# Sequential_LEDs.net
KiCad netlist of a schematic drawn in Altium Designer
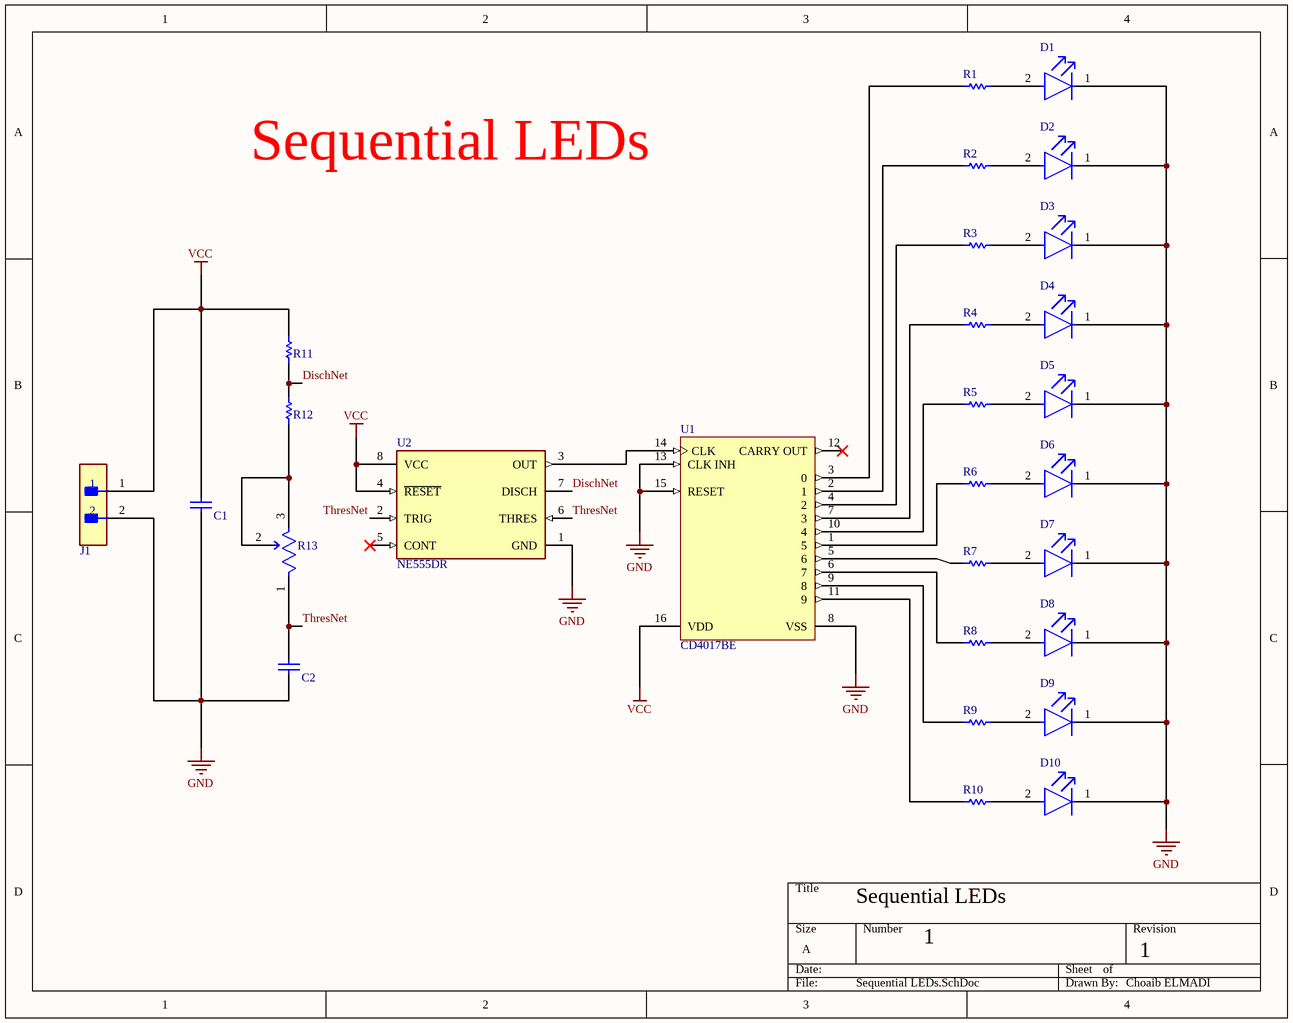
[diagram p0: Sequential LEDs.SchDoc]

(export (version "E")
  (design (tool "Eeschema 10.0.6"))
  (components
    (comp (ref "C1")
      (value "C0805C105K3RACTU")
      (footprint "CAPC2013X140X50LL20T25")
      (fields (field (name "MANUFACTURER") "Kemet"))
      (libsource (lib "Altium Content Vault") (part "CAP"))
    )
    (comp (ref "C2")
      (value "C0805C105K3RACTU")
      (footprint "CAPC2013X140X50LL20T25")
      (fields (field (name "MANUFACTURER") "Kemet"))
      (libsource (lib "Altium Content Vault") (part "CAP"))
    )
    (comp (ref "D1")
      (value "HLMP-1301")
      (footprint "FP-HLMP-1301-MFG")
      (description "LED RED DIFFUSED T-1 T/H")
      (fields
        (field (name "OCTOPART") "https://octopart.com/hlmp-1301-broadcom-71130345")
        (field (name "MANUFACTURER") "Broadcom")
      )
      (libsource (lib "Altium Content Vault") (part "8706943c75ba83719d021d2fdc84c58"))
    )
    (comp (ref "D2")
      (value "HLMP-1301")
      (footprint "FP-HLMP-1301-MFG")
      (description "LED RED DIFFUSED T-1 T/H")
      (fields
        (field (name "OCTOPART") "https://octopart.com/hlmp-1301-broadcom-71130345")
        (field (name "MANUFACTURER") "Broadcom")
      )
      (libsource (lib "Altium Content Vault") (part "8706943c75ba83719d021d2fdc84c58"))
    )
    (comp (ref "D3")
      (value "HLMP-1301")
      (footprint "FP-HLMP-1301-MFG")
      (description "LED RED DIFFUSED T-1 T/H")
      (fields
        (field (name "OCTOPART") "https://octopart.com/hlmp-1301-broadcom-71130345")
        (field (name "MANUFACTURER") "Broadcom")
      )
      (libsource (lib "Altium Content Vault") (part "8706943c75ba83719d021d2fdc84c58"))
    )
    (comp (ref "D4")
      (value "HLMP-1301")
      (footprint "FP-HLMP-1301-MFG")
      (description "LED RED DIFFUSED T-1 T/H")
      (fields
        (field (name "OCTOPART") "https://octopart.com/hlmp-1301-broadcom-71130345")
        (field (name "MANUFACTURER") "Broadcom")
      )
      (libsource (lib "Altium Content Vault") (part "8706943c75ba83719d021d2fdc84c58"))
    )
    (comp (ref "D5")
      (value "HLMP-1301")
      (footprint "FP-HLMP-1301-MFG")
      (description "LED RED DIFFUSED T-1 T/H")
      (fields
        (field (name "OCTOPART") "https://octopart.com/hlmp-1301-broadcom-71130345")
        (field (name "MANUFACTURER") "Broadcom")
      )
      (libsource (lib "Altium Content Vault") (part "8706943c75ba83719d021d2fdc84c58"))
    )
    (comp (ref "D6")
      (value "HLMP-1301")
      (footprint "FP-HLMP-1301-MFG")
      (description "LED RED DIFFUSED T-1 T/H")
      (fields
        (field (name "OCTOPART") "https://octopart.com/hlmp-1301-broadcom-71130345")
        (field (name "MANUFACTURER") "Broadcom")
      )
      (libsource (lib "Altium Content Vault") (part "8706943c75ba83719d021d2fdc84c58"))
    )
    (comp (ref "D7")
      (value "HLMP-1301")
      (footprint "FP-HLMP-1301-MFG")
      (description "LED RED DIFFUSED T-1 T/H")
      (fields
        (field (name "OCTOPART") "https://octopart.com/hlmp-1301-broadcom-71130345")
        (field (name "MANUFACTURER") "Broadcom")
      )
      (libsource (lib "Altium Content Vault") (part "8706943c75ba83719d021d2fdc84c58"))
    )
    (comp (ref "D8")
      (value "HLMP-1301")
      (footprint "FP-HLMP-1301-MFG")
      (description "LED RED DIFFUSED T-1 T/H")
      (fields
        (field (name "OCTOPART") "https://octopart.com/hlmp-1301-broadcom-71130345")
        (field (name "MANUFACTURER") "Broadcom")
      )
      (libsource (lib "Altium Content Vault") (part "8706943c75ba83719d021d2fdc84c58"))
    )
    (comp (ref "D9")
      (value "HLMP-1301")
      (footprint "FP-HLMP-1301-MFG")
      (description "LED RED DIFFUSED T-1 T/H")
      (fields
        (field (name "OCTOPART") "https://octopart.com/hlmp-1301-broadcom-71130345")
        (field (name "MANUFACTURER") "Broadcom")
      )
      (libsource (lib "Altium Content Vault") (part "8706943c75ba83719d021d2fdc84c58"))
    )
    (comp (ref "D10")
      (value "HLMP-1301")
      (footprint "FP-HLMP-1301-MFG")
      (description "LED RED DIFFUSED T-1 T/H")
      (fields
        (field (name "OCTOPART") "https://octopart.com/hlmp-1301-broadcom-71130345")
        (field (name "MANUFACTURER") "Broadcom")
      )
      (libsource (lib "Altium Content Vault") (part "8706943c75ba83719d021d2fdc84c58"))
    )
    (comp (ref "J1")
      (value "M20-9990245")
      (footprint "FP-M20-9990245-MFG")
      (description "CONN HEADER VERT 2POS 2.54MM")
      (fields (field (name "VOLTAGE") "50V"))
      (libsource (lib "Altium Content Vault") (part "3bc925449376181038e59eaffc5286c"))
    )
    (comp (ref "R1")
      (value "RC0805FR-071KL")
      (footprint "RESC2013X60X35ML10T20")
      (description "Chip Resistor, 1 KOhm, +/- 1%, 125 mW, -55 to 155 degC, 0805 (2012 Metric), RoHS, Tape and Reel")
      (fields (field (name "TOLERANCE") "1%") (field (name "MANUFACTURER") "Yageo"))
      (libsource (lib "Altium Content Vault") (part "RES-2"))
    )
    (comp (ref "R2")
      (value "RC0805FR-071KL")
      (footprint "RESC2013X60X35ML10T20")
      (description "Chip Resistor, 1 KOhm, +/- 1%, 125 mW, -55 to 155 degC, 0805 (2012 Metric), RoHS, Tape and Reel")
      (fields (field (name "TOLERANCE") "1%") (field (name "MANUFACTURER") "Yageo"))
      (libsource (lib "Altium Content Vault") (part "RES-2"))
    )
    (comp (ref "R3")
      (value "RC0805FR-071KL")
      (footprint "RESC2013X60X35ML10T20")
      (description "Chip Resistor, 1 KOhm, +/- 1%, 125 mW, -55 to 155 degC, 0805 (2012 Metric), RoHS, Tape and Reel")
      (fields (field (name "TOLERANCE") "1%") (field (name "MANUFACTURER") "Yageo"))
      (libsource (lib "Altium Content Vault") (part "RES-2"))
    )
    (comp (ref "R4")
      (value "RC0805FR-071KL")
      (footprint "RESC2013X60X35ML10T20")
      (description "Chip Resistor, 1 KOhm, +/- 1%, 125 mW, -55 to 155 degC, 0805 (2012 Metric), RoHS, Tape and Reel")
      (fields (field (name "TOLERANCE") "1%") (field (name "MANUFACTURER") "Yageo"))
      (libsource (lib "Altium Content Vault") (part "RES-2"))
    )
    (comp (ref "R5")
      (value "RC0805FR-071KL")
      (footprint "RESC2013X60X35ML10T20")
      (description "Chip Resistor, 1 KOhm, +/- 1%, 125 mW, -55 to 155 degC, 0805 (2012 Metric), RoHS, Tape and Reel")
      (fields (field (name "TOLERANCE") "1%") (field (name "MANUFACTURER") "Yageo"))
      (libsource (lib "Altium Content Vault") (part "RES-2"))
    )
    (comp (ref "R6")
      (value "RC0805FR-071KL")
      (footprint "RESC2013X60X35ML10T20")
      (description "Chip Resistor, 1 KOhm, +/- 1%, 125 mW, -55 to 155 degC, 0805 (2012 Metric), RoHS, Tape and Reel")
      (fields (field (name "TOLERANCE") "1%") (field (name "MANUFACTURER") "Yageo"))
      (libsource (lib "Altium Content Vault") (part "RES-2"))
    )
    (comp (ref "R7")
      (value "RC0805FR-071KL")
      (footprint "RESC2013X60X35ML10T20")
      (description "Chip Resistor, 1 KOhm, +/- 1%, 125 mW, -55 to 155 degC, 0805 (2012 Metric), RoHS, Tape and Reel")
      (fields (field (name "TOLERANCE") "1%") (field (name "MANUFACTURER") "Yageo"))
      (libsource (lib "Altium Content Vault") (part "RES-2"))
    )
    (comp (ref "R8")
      (value "RC0805FR-071KL")
      (footprint "RESC2013X60X35ML10T20")
      (description "Chip Resistor, 1 KOhm, +/- 1%, 125 mW, -55 to 155 degC, 0805 (2012 Metric), RoHS, Tape and Reel")
      (fields (field (name "TOLERANCE") "1%") (field (name "MANUFACTURER") "Yageo"))
      (libsource (lib "Altium Content Vault") (part "RES-2"))
    )
    (comp (ref "R9")
      (value "RC0805FR-071KL")
      (footprint "RESC2013X60X35ML10T20")
      (description "Chip Resistor, 1 KOhm, +/- 1%, 125 mW, -55 to 155 degC, 0805 (2012 Metric), RoHS, Tape and Reel")
      (fields (field (name "TOLERANCE") "1%") (field (name "MANUFACTURER") "Yageo"))
      (libsource (lib "Altium Content Vault") (part "RES-2"))
    )
    (comp (ref "R10")
      (value "RC0805FR-071KL")
      (footprint "RESC2013X60X35ML10T20")
      (description "Chip Resistor, 1 KOhm, +/- 1%, 125 mW, -55 to 155 degC, 0805 (2012 Metric), RoHS, Tape and Reel")
      (fields (field (name "TOLERANCE") "1%") (field (name "MANUFACTURER") "Yageo"))
      (libsource (lib "Altium Content Vault") (part "RES-2"))
    )
    (comp (ref "R11")
      (value "RC0805FR-071KL")
      (footprint "RESC2013X60X35ML10T20")
      (description "Chip Resistor, 1 KOhm, +/- 1%, 125 mW, -55 to 155 degC, 0805 (2012 Metric), RoHS, Tape and Reel")
      (fields (field (name "TOLERANCE") "1%") (field (name "MANUFACTURER") "Yageo"))
      (libsource (lib "Altium Content Vault") (part "RES-2"))
    )
    (comp (ref "R12")
      (value "RC0805FR-071KL")
      (footprint "RESC2013X60X35ML10T20")
      (description "Chip Resistor, 1 KOhm, +/- 1%, 125 mW, -55 to 155 degC, 0805 (2012 Metric), RoHS, Tape and Reel")
      (fields (field (name "TOLERANCE") "1%") (field (name "MANUFACTURER") "Yageo"))
      (libsource (lib "Altium Content Vault") (part "RES-2"))
    )
    (comp (ref "R13")
      (value "3386P-1-105TLF")
      (footprint "FP-3386P-MFG")
      (description "TRIMMER 1M OHM 0.5W PC PIN TOP")
      (fields (field (name "TOLERANCE") "10%") (field (name "MANUFACTURER") "Bourns Inc."))
      (libsource (lib "Altium Content Vault") (part "2dcfd2547301a7d3209a5e99acfd772"))
    )
    (comp (ref "U1")
      (value "CD4017BE")
      (footprint "N0016A")
      (description "CMOS Decade Counter with 10 Decoded Outputs, N0016A, TUBE")
      (fields
        (field (name "MANUFACTURER") "Texas Instruments")
        (field (name "GENERIC PART NUMBER") "CD4017B")
      )
      (libsource (lib "Altium Content Vault") (part "TI-CD4017B-16"))
    )
    (comp (ref "U2")
      (value "NE555DR")
      (footprint "FP-D0008A-IPC_A")
      (description "IC OSC SGL TIMER 100KHZ 8-SOIC")
      (libsource (lib "Altium Content Vault") (part "a29bba90211dec1890110b94dad7d53"))
    )
  )
  (nets
    (net (code "1") (name "/DischNet") (class "Default")
      (node (ref "R11") (pin "1") (pinfunction "1_1") (pintype "passive"))
      (node (ref "R12") (pin "2") (pinfunction "2_2") (pintype "passive"))
      (node (ref "U2") (pin "7") (pinfunction "DISCH_7") (pintype "open_collector"))
    )
    (net (code "2") (name "/ThresNet") (class "Default")
      (node (ref "C2") (pin "2") (pinfunction "2_2") (pintype "passive"))
      (node (ref "R13") (pin "1") (pinfunction "CCW_1") (pintype "passive"))
      (node (ref "U2") (pin "2") (pinfunction "TRIG_2") (pintype "input"))
      (node (ref "U2") (pin "6") (pinfunction "THRES_6") (pintype "input"))
    )
    (net (code "3") (name "GND") (class "Default")
      (node (ref "C1") (pin "1") (pinfunction "1_1") (pintype "passive"))
      (node (ref "C2") (pin "1") (pinfunction "1_1") (pintype "passive"))
      (node (ref "D1") (pin "1") (pinfunction "C_1") (pintype "passive"))
      (node (ref "D10") (pin "1") (pinfunction "C_1") (pintype "passive"))
      (node (ref "D2") (pin "1") (pinfunction "C_1") (pintype "passive"))
      (node (ref "D3") (pin "1") (pinfunction "C_1") (pintype "passive"))
      (node (ref "D4") (pin "1") (pinfunction "C_1") (pintype "passive"))
      (node (ref "D5") (pin "1") (pinfunction "C_1") (pintype "passive"))
      (node (ref "D6") (pin "1") (pinfunction "C_1") (pintype "passive"))
      (node (ref "D7") (pin "1") (pinfunction "C_1") (pintype "passive"))
      (node (ref "D8") (pin "1") (pinfunction "C_1") (pintype "passive"))
      (node (ref "D9") (pin "1") (pinfunction "C_1") (pintype "passive"))
      (node (ref "J1") (pin "2") (pinfunction "2_2") (pintype "passive"))
      (node (ref "U1") (pin "13") (pinfunction "CLK_INH_13") (pintype "input"))
      (node (ref "U1") (pin "15") (pinfunction "RESET_15") (pintype "input"))
      (node (ref "U1") (pin "8") (pinfunction "VSS_8") (pintype "power_in"))
      (node (ref "U2") (pin "1") (pinfunction "GND_1") (pintype "power_in"))
    )
    (net (code "4") (name "Net-(D1-A)") (class "Default")
      (node (ref "D1") (pin "2") (pinfunction "A_2") (pintype "passive"))
      (node (ref "R1") (pin "2") (pinfunction "2_2") (pintype "passive"))
    )
    (net (code "5") (name "Net-(D2-A)") (class "Default")
      (node (ref "D2") (pin "2") (pinfunction "A_2") (pintype "passive"))
      (node (ref "R2") (pin "2") (pinfunction "2_2") (pintype "passive"))
    )
    (net (code "6") (name "Net-(D3-A)") (class "Default")
      (node (ref "D3") (pin "2") (pinfunction "A_2") (pintype "passive"))
      (node (ref "R3") (pin "2") (pinfunction "2_2") (pintype "passive"))
    )
    (net (code "7") (name "Net-(D4-A)") (class "Default")
      (node (ref "D4") (pin "2") (pinfunction "A_2") (pintype "passive"))
      (node (ref "R4") (pin "2") (pinfunction "2_2") (pintype "passive"))
    )
    (net (code "8") (name "Net-(D5-A)") (class "Default")
      (node (ref "D5") (pin "2") (pinfunction "A_2") (pintype "passive"))
      (node (ref "R5") (pin "2") (pinfunction "2_2") (pintype "passive"))
    )
    (net (code "9") (name "Net-(D6-A)") (class "Default")
      (node (ref "D6") (pin "2") (pinfunction "A_2") (pintype "passive"))
      (node (ref "R6") (pin "2") (pinfunction "2_2") (pintype "passive"))
    )
    (net (code "10") (name "Net-(D7-A)") (class "Default")
      (node (ref "D7") (pin "2") (pinfunction "A_2") (pintype "passive"))
      (node (ref "R7") (pin "2") (pinfunction "2_2") (pintype "passive"))
    )
    (net (code "11") (name "Net-(D8-A)") (class "Default")
      (node (ref "D8") (pin "2") (pinfunction "A_2") (pintype "passive"))
      (node (ref "R8") (pin "2") (pinfunction "2_2") (pintype "passive"))
    )
    (net (code "12") (name "Net-(D9-A)") (class "Default")
      (node (ref "D9") (pin "2") (pinfunction "A_2") (pintype "passive"))
      (node (ref "R9") (pin "2") (pinfunction "2_2") (pintype "passive"))
    )
    (net (code "13") (name "Net-(D10-A)") (class "Default")
      (node (ref "D10") (pin "2") (pinfunction "A_2") (pintype "passive"))
      (node (ref "R10") (pin "2") (pinfunction "2_2") (pintype "passive"))
    )
    (net (code "14") (name "Net-(R13-CW)") (class "Default")
      (node (ref "R12") (pin "1") (pinfunction "1_1") (pintype "passive"))
      (node (ref "R13") (pin "2") (pinfunction "WIPER_2") (pintype "passive"))
      (node (ref "R13") (pin "3") (pinfunction "CW_3") (pintype "passive"))
    )
    (net (code "15") (name "Net-(U1-0)") (class "Default")
      (node (ref "R1") (pin "1") (pinfunction "1_1") (pintype "passive"))
      (node (ref "U1") (pin "3") (pinfunction "0_3") (pintype "output"))
    )
    (net (code "16") (name "Net-(U1-1)") (class "Default")
      (node (ref "R2") (pin "1") (pinfunction "1_1") (pintype "passive"))
      (node (ref "U1") (pin "2") (pinfunction "1_2") (pintype "output"))
    )
    (net (code "17") (name "Net-(U1-2)") (class "Default")
      (node (ref "R3") (pin "1") (pinfunction "1_1") (pintype "passive"))
      (node (ref "U1") (pin "4") (pinfunction "2_4") (pintype "output"))
    )
    (net (code "18") (name "Net-(U1-3)") (class "Default")
      (node (ref "R4") (pin "1") (pinfunction "1_1") (pintype "passive"))
      (node (ref "U1") (pin "7") (pinfunction "3_7") (pintype "output"))
    )
    (net (code "19") (name "Net-(U1-4)") (class "Default")
      (node (ref "R5") (pin "1") (pinfunction "1_1") (pintype "passive"))
      (node (ref "U1") (pin "10") (pinfunction "4_10") (pintype "output"))
    )
    (net (code "20") (name "Net-(U1-5)") (class "Default")
      (node (ref "R6") (pin "1") (pinfunction "1_1") (pintype "passive"))
      (node (ref "U1") (pin "1") (pinfunction "5_1") (pintype "output"))
    )
    (net (code "21") (name "Net-(U1-6)") (class "Default")
      (node (ref "R7") (pin "1") (pinfunction "1_1") (pintype "passive"))
      (node (ref "U1") (pin "5") (pinfunction "6_5") (pintype "output"))
    )
    (net (code "22") (name "Net-(U1-7)") (class "Default")
      (node (ref "R8") (pin "1") (pinfunction "1_1") (pintype "passive"))
      (node (ref "U1") (pin "6") (pinfunction "7_6") (pintype "output"))
    )
    (net (code "23") (name "Net-(U1-8)") (class "Default")
      (node (ref "R9") (pin "1") (pinfunction "1_1") (pintype "passive"))
      (node (ref "U1") (pin "9") (pinfunction "8_9") (pintype "output"))
    )
    (net (code "24") (name "Net-(U1-9)") (class "Default")
      (node (ref "R10") (pin "1") (pinfunction "1_1") (pintype "passive"))
      (node (ref "U1") (pin "11") (pinfunction "9_11") (pintype "output"))
    )
    (net (code "25") (name "Net-(U1-CLK)") (class "Default")
      (node (ref "U1") (pin "14") (pinfunction "CLK_14") (pintype "input"))
      (node (ref "U2") (pin "3") (pinfunction "OUT_3") (pintype "output"))
    )
    (net (code "26") (name "VCC") (class "Default")
      (node (ref "C1") (pin "2") (pinfunction "2_2") (pintype "passive"))
      (node (ref "J1") (pin "1") (pinfunction "1_1") (pintype "passive"))
      (node (ref "R11") (pin "2") (pinfunction "2_2") (pintype "passive"))
      (node (ref "U1") (pin "16") (pinfunction "VDD_16") (pintype "power_in"))
      (node (ref "U2") (pin "4") (pinfunction "~{RESET}_4") (pintype "input"))
      (node (ref "U2") (pin "8") (pinfunction "VCC_8") (pintype "power_in"))
    )
    (net (code "27") (name "unconnected-(U1-CARRY_OUT-Pad12)") (class "Default")
      (node (ref "U1") (pin "12") (pinfunction "CARRY_OUT_12") (pintype "output+no_connect"))
    )
    (net (code "28") (name "unconnected-(U2-CONT-Pad5)") (class "Default")
      (node (ref "U2") (pin "5") (pinfunction "CONT_5") (pintype "input+no_connect"))
    )
  )
)
